# TXn_v1_2_toponly.net
KiCad netlist of a schematic drawn in EAGLE
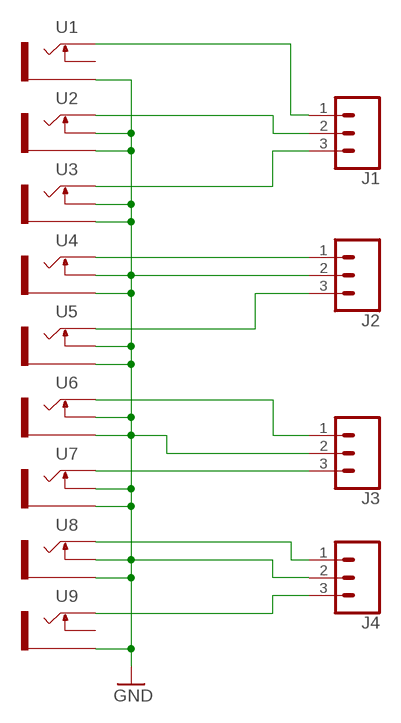
[diagram p0: schematic, sheet 1]

(export (version "E")
  (design (tool "Eeschema 10.0.6"))
  (components
    (comp (ref "J1")
      (value "CONN_031X03_NO_SILK")
      (footprint "eagle-import:1X03_NO_SILK")
      (libsource (lib "eagle-import") (part "CONN_031X03_NO_SILK"))
    )
    (comp (ref "J2")
      (value "CONN_031X03_NO_SILK")
      (footprint "eagle-import:1X03_NO_SILK")
      (libsource (lib "eagle-import") (part "CONN_031X03_NO_SILK"))
    )
    (comp (ref "J3")
      (value "CONN_031X03_NO_SILK")
      (footprint "eagle-import:1X03_NO_SILK")
      (libsource (lib "eagle-import") (part "CONN_031X03_NO_SILK"))
    )
    (comp (ref "J4")
      (value "CONN_031X03_NO_SILK")
      (footprint "eagle-import:1X03_NO_SILK")
      (libsource (lib "eagle-import") (part "CONN_031X03_NO_SILK"))
    )
    (comp (ref "U1")
      (value "THONKICONNLEFT")
      (footprint "eagle-import:WQP-PJ301M-12_JACK_L")
      (libsource (lib "eagle-import") (part "THONKICONNLEFT"))
    )
    (comp (ref "U2")
      (value "THONKICONNLEFT")
      (footprint "eagle-import:WQP-PJ301M-12_JACK_L")
      (libsource (lib "eagle-import") (part "THONKICONNLEFT"))
    )
    (comp (ref "U3")
      (value "THONKICONNLEFT")
      (footprint "eagle-import:WQP-PJ301M-12_JACK_L")
      (libsource (lib "eagle-import") (part "THONKICONNLEFT"))
    )
    (comp (ref "U4")
      (value "THONKICONNLEFT")
      (footprint "eagle-import:WQP-PJ301M-12_JACK_L")
      (libsource (lib "eagle-import") (part "THONKICONNLEFT"))
    )
    (comp (ref "U5")
      (value "THONKICONNLEFT")
      (footprint "eagle-import:WQP-PJ301M-12_JACK_L")
      (libsource (lib "eagle-import") (part "THONKICONNLEFT"))
    )
    (comp (ref "U6")
      (value "THONKICONNLEFT")
      (footprint "eagle-import:WQP-PJ301M-12_JACK_L")
      (libsource (lib "eagle-import") (part "THONKICONNLEFT"))
    )
    (comp (ref "U7")
      (value "THONKICONNLEFT")
      (footprint "eagle-import:WQP-PJ301M-12_JACK_L")
      (libsource (lib "eagle-import") (part "THONKICONNLEFT"))
    )
    (comp (ref "U8")
      (value "THONKICONNLEFT")
      (footprint "eagle-import:WQP-PJ301M-12_JACK_L")
      (libsource (lib "eagle-import") (part "THONKICONNLEFT"))
    )
    (comp (ref "U9")
      (value "THONKICONNLEFT")
      (footprint "eagle-import:WQP-PJ301M-12_JACK_L")
      (libsource (lib "eagle-import") (part "THONKICONNLEFT"))
    )
  )
  (nets
    (net (code "1") (name "GND") (class "Default")
      (node (ref "J2") (pin "2") (pinfunction "2_2") (pintype "passive"))
      (node (ref "J3") (pin "2") (pinfunction "2_2") (pintype "passive"))
      (node (ref "J4") (pin "2") (pinfunction "2_2") (pintype "passive"))
      (node (ref "U1") (pin "P$3_SLEEVE") (pinfunction "SLEEVE_P$3_SLEEVE") (pintype "passive"))
      (node (ref "U2") (pin "P$2_SWITCH") (pinfunction "SWITCH_P$2_SWITCH") (pintype "passive"))
      (node (ref "U2") (pin "P$3_SLEEVE") (pinfunction "SLEEVE_P$3_SLEEVE") (pintype "passive"))
      (node (ref "U3") (pin "P$2_SWITCH") (pinfunction "SWITCH_P$2_SWITCH") (pintype "passive"))
      (node (ref "U3") (pin "P$3_SLEEVE") (pinfunction "SLEEVE_P$3_SLEEVE") (pintype "passive"))
      (node (ref "U4") (pin "P$2_SWITCH") (pinfunction "SWITCH_P$2_SWITCH") (pintype "passive"))
      (node (ref "U4") (pin "P$3_SLEEVE") (pinfunction "SLEEVE_P$3_SLEEVE") (pintype "passive"))
      (node (ref "U5") (pin "P$2_SWITCH") (pinfunction "SWITCH_P$2_SWITCH") (pintype "passive"))
      (node (ref "U5") (pin "P$3_SLEEVE") (pinfunction "SLEEVE_P$3_SLEEVE") (pintype "passive"))
      (node (ref "U6") (pin "P$2_SWITCH") (pinfunction "SWITCH_P$2_SWITCH") (pintype "passive"))
      (node (ref "U6") (pin "P$3_SLEEVE") (pinfunction "SLEEVE_P$3_SLEEVE") (pintype "passive"))
      (node (ref "U7") (pin "P$2_SWITCH") (pinfunction "SWITCH_P$2_SWITCH") (pintype "passive"))
      (node (ref "U7") (pin "P$3_SLEEVE") (pinfunction "SLEEVE_P$3_SLEEVE") (pintype "passive"))
      (node (ref "U8") (pin "P$2_SWITCH") (pinfunction "SWITCH_P$2_SWITCH") (pintype "passive"))
      (node (ref "U8") (pin "P$3_SLEEVE") (pinfunction "SLEEVE_P$3_SLEEVE") (pintype "passive"))
      (node (ref "U9") (pin "P$3_SLEEVE") (pinfunction "SLEEVE_P$3_SLEEVE") (pintype "passive"))
    )
    (net (code "2") (name "Net-(U1-TIP)") (class "Default")
      (node (ref "J1") (pin "1") (pinfunction "1_1") (pintype "passive"))
      (node (ref "U1") (pin "P$1_TIP") (pinfunction "TIP_P$1_TIP") (pintype "passive"))
    )
    (net (code "3") (name "Net-(U2-TIP)") (class "Default")
      (node (ref "J1") (pin "2") (pinfunction "2_2") (pintype "passive"))
      (node (ref "U2") (pin "P$1_TIP") (pinfunction "TIP_P$1_TIP") (pintype "passive"))
    )
    (net (code "4") (name "Net-(U3-TIP)") (class "Default")
      (node (ref "J1") (pin "3") (pinfunction "3_3") (pintype "passive"))
      (node (ref "U3") (pin "P$1_TIP") (pinfunction "TIP_P$1_TIP") (pintype "passive"))
    )
    (net (code "5") (name "Net-(U4-TIP)") (class "Default")
      (node (ref "J2") (pin "1") (pinfunction "1_1") (pintype "passive"))
      (node (ref "U4") (pin "P$1_TIP") (pinfunction "TIP_P$1_TIP") (pintype "passive"))
    )
    (net (code "6") (name "Net-(U5-TIP)") (class "Default")
      (node (ref "J2") (pin "3") (pinfunction "3_3") (pintype "passive"))
      (node (ref "U5") (pin "P$1_TIP") (pinfunction "TIP_P$1_TIP") (pintype "passive"))
    )
    (net (code "7") (name "Net-(U6-TIP)") (class "Default")
      (node (ref "J3") (pin "1") (pinfunction "1_1") (pintype "passive"))
      (node (ref "U6") (pin "P$1_TIP") (pinfunction "TIP_P$1_TIP") (pintype "passive"))
    )
    (net (code "8") (name "Net-(U7-TIP)") (class "Default")
      (node (ref "J3") (pin "3") (pinfunction "3_3") (pintype "passive"))
      (node (ref "U7") (pin "P$1_TIP") (pinfunction "TIP_P$1_TIP") (pintype "passive"))
    )
    (net (code "9") (name "Net-(U8-TIP)") (class "Default")
      (node (ref "J4") (pin "1") (pinfunction "1_1") (pintype "passive"))
      (node (ref "U8") (pin "P$1_TIP") (pinfunction "TIP_P$1_TIP") (pintype "passive"))
    )
    (net (code "10") (name "Net-(U9-TIP)") (class "Default")
      (node (ref "J4") (pin "3") (pinfunction "3_3") (pintype "passive"))
      (node (ref "U9") (pin "P$1_TIP") (pinfunction "TIP_P$1_TIP") (pintype "passive"))
    )
    (net (code "11") (name "unconnected-(U1-SWITCH-PadP$2_SWITCH)") (class "Default")
      (node (ref "U1") (pin "P$2_SWITCH") (pinfunction "SWITCH_P$2_SWITCH") (pintype "passive"))
    )
    (net (code "12") (name "unconnected-(U9-SWITCH-PadP$2_SWITCH)") (class "Default")
      (node (ref "U9") (pin "P$2_SWITCH") (pinfunction "SWITCH_P$2_SWITCH") (pintype "passive"))
    )
  )
)
